# 4x7-segments_Arduino_shield.net
KiCad netlist of a schematic drawn in EAGLE
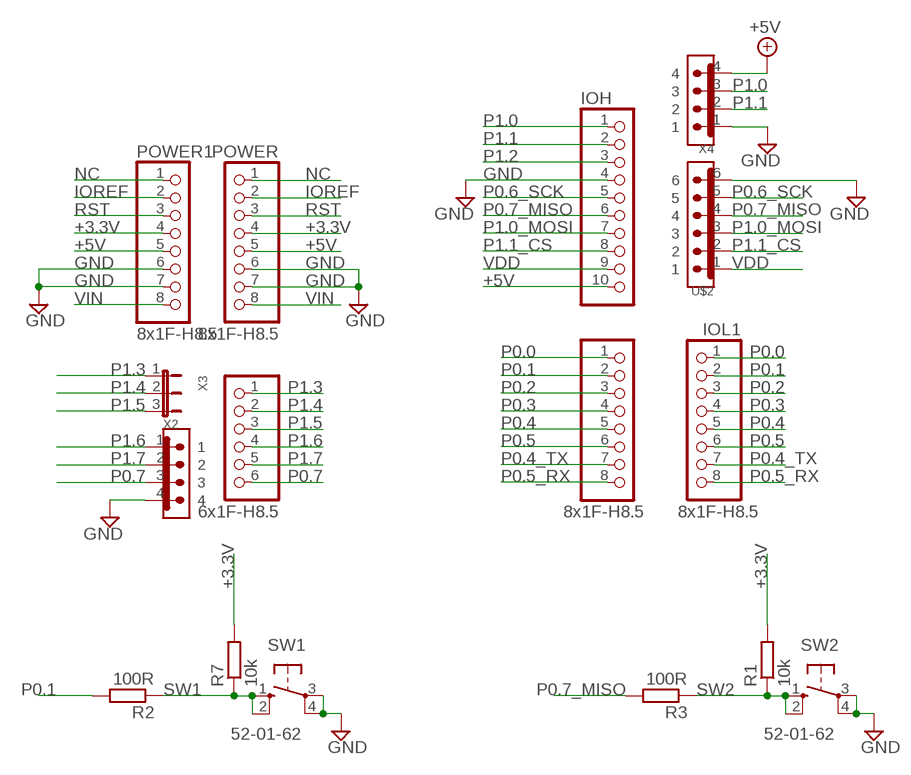
[diagram p0: schematic, sheet 1]
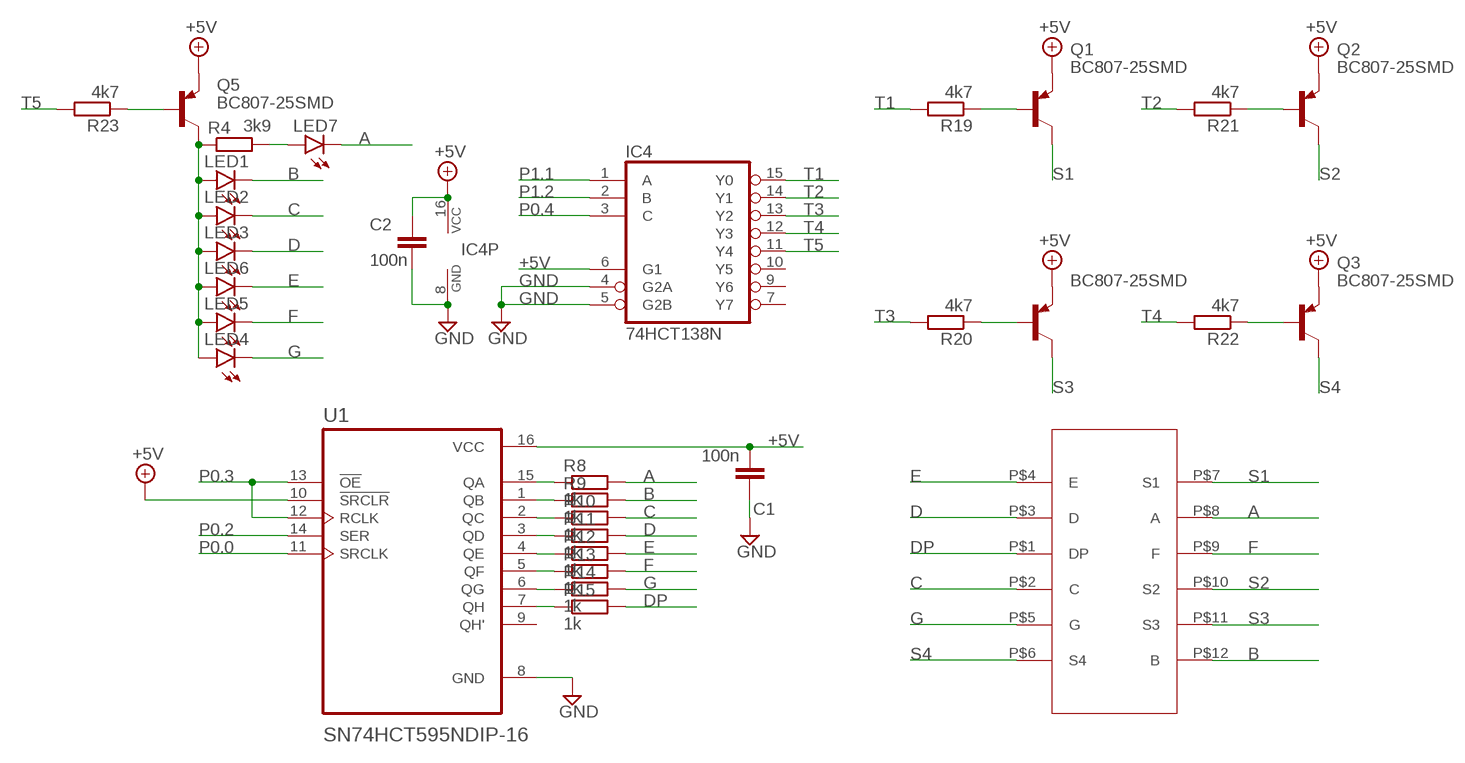
[diagram p1: schematic, sheet 2]
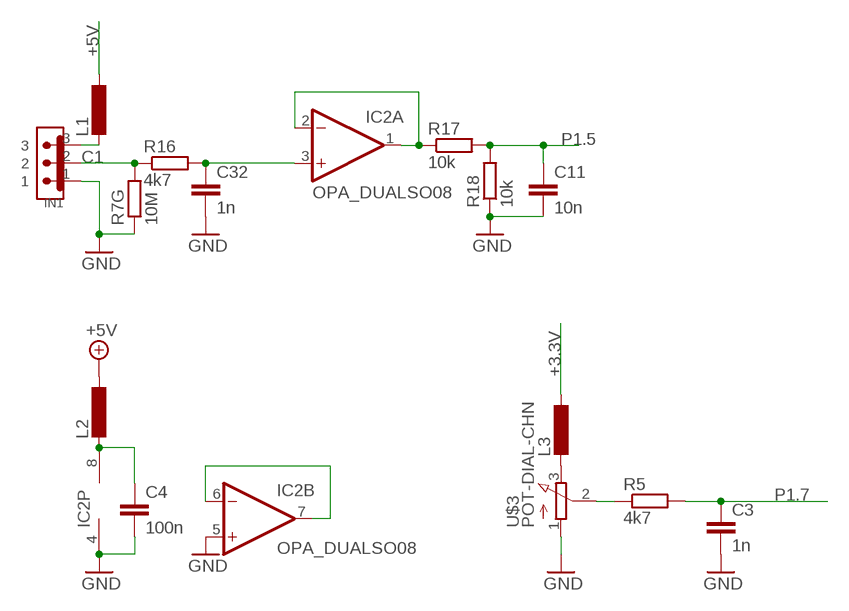
[diagram p2: schematic, sheet 3]

(export (version "E")
  (design (tool "Eeschema 10.0.6"))
  (components
    (comp (ref "AD")
      (value "6x1F-H8.5")
      (footprint "eagle-import:1X06")
      (libsource (lib "eagle-import") (part "PINHD-1X6"))
    )
    (comp (ref "IOH")
      (value "10x1F-H8.5")
      (footprint "eagle-import:1X10")
      (libsource (lib "eagle-import") (part "PINHD-1X10_ARD"))
    )
    (comp (ref "IOL")
      (value "8x1F-H8.5")
      (footprint "eagle-import:1X08")
      (libsource (lib "eagle-import") (part "PINHD-1X8"))
    )
    (comp (ref "IOL1")
      (value "8x1F-H8.5")
      (footprint "eagle-import:1X08")
      (libsource (lib "eagle-import") (part "PINHD-1X8"))
    )
    (comp (ref "POWER")
      (value "8x1F-H8.5")
      (footprint "eagle-import:1X08")
      (libsource (lib "eagle-import") (part "PINHD-1X8"))
    )
    (comp (ref "POWER1")
      (value "8x1F-H8.5")
      (footprint "eagle-import:1X08")
      (libsource (lib "eagle-import") (part "PINHD-1X8"))
    )
    (comp (ref "R1")
      (value "10k")
      (footprint "eagle-import:R0805")
      (libsource (lib "eagle-import") (part "Zoli2_R0805"))
    )
    (comp (ref "R2")
      (value "100R")
      (footprint "eagle-import:R0805")
      (libsource (lib "eagle-import") (part "R0805"))
    )
    (comp (ref "R3")
      (value "100R")
      (footprint "eagle-import:R0805")
      (libsource (lib "eagle-import") (part "R0805"))
    )
    (comp (ref "R7")
      (value "10k")
      (footprint "eagle-import:R0805")
      (libsource (lib "eagle-import") (part "Zoli2_R0805"))
    )
    (comp (ref "SW1")
      (value "52-01-62")
      (footprint "eagle-import:B3F-10XX")
      (fields (field (name "MPN") "B3F-1000"))
      (libsource (lib "eagle-import") (part "10-XX"))
    )
    (comp (ref "SW2")
      (value "52-01-62")
      (footprint "eagle-import:B3F-10XX")
      (fields (field (name "MPN") "B3F-1000"))
      (libsource (lib "eagle-import") (part "10-XX"))
    )
    (comp (ref "U$2")
      (value "MOLEX6")
      (footprint "eagle-import:MOLEXV6")
      (libsource (lib "eagle-import") (part "MOLEX6"))
    )
    (comp (ref "X2")
      (value "MOLEX4V")
      (footprint "eagle-import:MOLEXV4")
      (libsource (lib "eagle-import") (part "MOLEX4V"))
    )
    (comp (ref "X3")
      (value "JP2E")
      (footprint "eagle-import:JP2")
      (libsource (lib "eagle-import") (part "JP2E"))
    )
    (comp (ref "X4")
      (value "MOLEX4V")
      (footprint "eagle-import:MOLEXV4")
      (libsource (lib "eagle-import") (part "MOLEX4V"))
    )
    (comp (ref "C3")
      (value "1n")
      (footprint "eagle-import:C0805")
      (libsource (lib "eagle-import") (part "Zoli_C0805"))
    )
    (comp (ref "C4")
      (value "100n")
      (footprint "eagle-import:C0805")
      (libsource (lib "eagle-import") (part "Zoli2_C0805"))
    )
    (comp (ref "C11")
      (value "10n")
      (footprint "eagle-import:C0805")
      (libsource (lib "eagle-import") (part "C0805"))
    )
    (comp (ref "C32")
      (value "1n")
      (footprint "eagle-import:C0805")
      (libsource (lib "eagle-import") (part "Zoli_C0805"))
    )
    (comp (ref "IC2")
      (value "OPA_DUALSO08")
      (footprint "eagle-import:SO08")
      (libsource (lib "eagle-import") (part "OPA_DUALSO08"))
    )
    (comp (ref "IN1")
      (value "MOLEX3V")
      (footprint "eagle-import:MOLEXV3")
      (libsource (lib "eagle-import") (part "MOLEX3V"))
    )
    (comp (ref "L1")
      (value "L0805")
      (footprint "eagle-import:R0805")
      (libsource (lib "eagle-import") (part "L0805"))
    )
    (comp (ref "L2")
      (value "L0805")
      (footprint "eagle-import:R0805")
      (libsource (lib "eagle-import") (part "L0805"))
    )
    (comp (ref "L3")
      (value "L0805")
      (footprint "eagle-import:R0805")
      (libsource (lib "eagle-import") (part "L0805"))
    )
    (comp (ref "R5")
      (value "4k7")
      (footprint "eagle-import:R0805")
      (libsource (lib "eagle-import") (part "R0805"))
    )
    (comp (ref "R7G")
      (value "10M")
      (footprint "eagle-import:R0805")
      (libsource (lib "eagle-import") (part "R0805"))
    )
    (comp (ref "R16")
      (value "4k7")
      (footprint "eagle-import:R0805")
      (libsource (lib "eagle-import") (part "R0805"))
    )
    (comp (ref "R17")
      (value "10k")
      (footprint "eagle-import:R1206")
      (libsource (lib "eagle-import") (part "Zoli2_R1206"))
    )
    (comp (ref "R18")
      (value "10k")
      (footprint "eagle-import:R1206")
      (libsource (lib "eagle-import") (part "Zoli2_R1206"))
    )
    (comp (ref "U$3")
      (value "POT-DIAL-CHN")
      (footprint "eagle-import:POT5")
      (libsource (lib "eagle-import") (part "POT-DIAL-CHN"))
    )
    (comp (ref "C1")
      (value "100n")
      (footprint "eagle-import:C0805")
      (libsource (lib "eagle-import") (part "Zoli_C0805"))
    )
    (comp (ref "C2")
      (value "100n")
      (footprint "eagle-import:C0805")
      (libsource (lib "eagle-import") (part "Zoli_C0805"))
    )
    (comp (ref "IC4")
      (value "74HCT138N")
      (footprint "eagle-import:DIL16")
      (libsource (lib "eagle-import") (part "74138NHC"))
    )
    (comp (ref "LED1")
      (value "LEDCHIPLED_1206")
      (footprint "eagle-import:CHIPLED_1206")
      (libsource (lib "eagle-import") (part "LEDCHIPLED_1206"))
    )
    (comp (ref "LED2")
      (value "LEDCHIPLED_1206")
      (footprint "eagle-import:CHIPLED_1206")
      (libsource (lib "eagle-import") (part "LEDCHIPLED_1206"))
    )
    (comp (ref "LED3")
      (value "LEDCHIPLED_1206")
      (footprint "eagle-import:CHIPLED_1206")
      (libsource (lib "eagle-import") (part "LEDCHIPLED_1206"))
    )
    (comp (ref "LED4")
      (value "LEDCHIPLED_1206")
      (footprint "eagle-import:CHIPLED_1206")
      (libsource (lib "eagle-import") (part "LEDCHIPLED_1206"))
    )
    (comp (ref "LED5")
      (value "LEDCHIPLED_1206")
      (footprint "eagle-import:CHIPLED_1206")
      (libsource (lib "eagle-import") (part "LEDCHIPLED_1206"))
    )
    (comp (ref "LED6")
      (value "LEDCHIPLED_1206")
      (footprint "eagle-import:CHIPLED_1206")
      (libsource (lib "eagle-import") (part "LEDCHIPLED_1206"))
    )
    (comp (ref "LED7")
      (value "LEDCHIPLED_1206")
      (footprint "eagle-import:CHIPLED_1206")
      (libsource (lib "eagle-import") (part "LEDCHIPLED_1206"))
    )
    (comp (ref "Q1")
      (value "BC807-25SMD")
      (footprint "eagle-import:SOT23-BEC")
      (libsource (lib "eagle-import") (part "BC807SMD-25"))
    )
    (comp (ref "Q2")
      (value "BC807-25SMD")
      (footprint "eagle-import:SOT23-BEC")
      (libsource (lib "eagle-import") (part "BC807SMD-25"))
    )
    (comp (ref "Q3")
      (value "BC807-25SMD")
      (footprint "eagle-import:SOT23-BEC")
      (libsource (lib "eagle-import") (part "BC807SMD-25"))
    )
    (comp (ref "Q4")
      (value "BC807-25SMD")
      (footprint "eagle-import:SOT23-BEC")
      (libsource (lib "eagle-import") (part "BC807SMD-25"))
    )
    (comp (ref "Q5")
      (value "BC807-25SMD")
      (footprint "eagle-import:SOT23-BEC")
      (libsource (lib "eagle-import") (part "BC807SMD-25"))
    )
    (comp (ref "R4")
      (value "3k9")
      (footprint "eagle-import:R1206")
      (libsource (lib "eagle-import") (part "R1206"))
    )
    (comp (ref "R8")
      (value "1k")
      (footprint "eagle-import:R1206")
      (libsource (lib "eagle-import") (part "R1206"))
    )
    (comp (ref "R9")
      (value "1k")
      (footprint "eagle-import:R1206")
      (libsource (lib "eagle-import") (part "R1206"))
    )
    (comp (ref "R10")
      (value "1k")
      (footprint "eagle-import:R1206")
      (libsource (lib "eagle-import") (part "R1206"))
    )
    (comp (ref "R11")
      (value "1k")
      (footprint "eagle-import:R1206")
      (libsource (lib "eagle-import") (part "R1206"))
    )
    (comp (ref "R12")
      (value "1k")
      (footprint "eagle-import:R1206")
      (libsource (lib "eagle-import") (part "R1206"))
    )
    (comp (ref "R13")
      (value "1k")
      (footprint "eagle-import:R1206")
      (libsource (lib "eagle-import") (part "R1206"))
    )
    (comp (ref "R14")
      (value "1k")
      (footprint "eagle-import:R1206")
      (libsource (lib "eagle-import") (part "R1206"))
    )
    (comp (ref "R15")
      (value "1k")
      (footprint "eagle-import:R1206")
      (libsource (lib "eagle-import") (part "R1206"))
    )
    (comp (ref "R19")
      (value "4k7")
      (footprint "eagle-import:R0805")
      (libsource (lib "eagle-import") (part "R0805"))
    )
    (comp (ref "R20")
      (value "4k7")
      (footprint "eagle-import:R0805")
      (libsource (lib "eagle-import") (part "R0805"))
    )
    (comp (ref "R21")
      (value "4k7")
      (footprint "eagle-import:R0805")
      (libsource (lib "eagle-import") (part "R0805"))
    )
    (comp (ref "R22")
      (value "4k7")
      (footprint "eagle-import:R0805")
      (libsource (lib "eagle-import") (part "R0805"))
    )
    (comp (ref "R23")
      (value "4k7")
      (footprint "eagle-import:R0805")
      (libsource (lib "eagle-import") (part "R0805"))
    )
    (comp (ref "U$1")
      (value "SH5461AS")
      (footprint "eagle-import:SH5461AS")
      (libsource (lib "eagle-import") (part "SH5461AS"))
    )
    (comp (ref "U1")
      (value "SN74HCT595NDIP-16")
      (footprint "eagle-import:DIP794W45P254L1969H508Q16")
      (fields (field (name "MF") "Texas Instruments") (field (name "MP") "SN74HC595N"))
      (libsource (lib "eagle-import") (part "SN74HC595NDIP-16"))
    )
  )
  (nets
    (net (code "1") (name "+3.3V") (class "Default")
      (node (ref "L3") (pin "2") (pinfunction "2_2") (pintype "passive"))
      (node (ref "POWER") (pin "4") (pinfunction "4_4") (pintype "passive"))
      (node (ref "POWER1") (pin "4") (pinfunction "4_4") (pintype "passive"))
      (node (ref "R1") (pin "2") (pinfunction "2_2") (pintype "passive"))
      (node (ref "R7") (pin "2") (pinfunction "2_2") (pintype "passive"))
    )
    (net (code "2") (name "+5V") (class "Default")
      (node (ref "C1") (pin "1") (pinfunction "1_1") (pintype "passive"))
      (node (ref "C2") (pin "2") (pinfunction "2_2") (pintype "passive"))
      (node (ref "IC4") (pin "16") (pinfunction "VCC_16") (pintype "power_in"))
      (node (ref "IC4") (pin "6") (pinfunction "G1_6") (pintype "input"))
      (node (ref "IOH") (pin "10") (pinfunction "10_10") (pintype "passive"))
      (node (ref "L1") (pin "2") (pinfunction "2_2") (pintype "passive"))
      (node (ref "L2") (pin "2") (pinfunction "2_2") (pintype "passive"))
      (node (ref "POWER") (pin "5") (pinfunction "5_5") (pintype "passive"))
      (node (ref "POWER1") (pin "5") (pinfunction "5_5") (pintype "passive"))
      (node (ref "Q1") (pin "E") (pinfunction "E_E") (pintype "passive"))
      (node (ref "Q2") (pin "E") (pinfunction "E_E") (pintype "passive"))
      (node (ref "Q3") (pin "E") (pinfunction "E_E") (pintype "passive"))
      (node (ref "Q4") (pin "E") (pinfunction "E_E") (pintype "passive"))
      (node (ref "Q5") (pin "E") (pinfunction "E_E") (pintype "passive"))
      (node (ref "U1") (pin "10") (pinfunction "~{SRCLR}_10") (pintype "input"))
      (node (ref "U1") (pin "16") (pinfunction "VCC_16") (pintype "power_in"))
      (node (ref "X4") (pin "4") (pinfunction "4_4") (pintype "bidirectional"))
    )
    (net (code "3") (name "A") (class "Default")
      (node (ref "LED7") (pin "C") (pinfunction "C_C") (pintype "passive"))
      (node (ref "R8") (pin "2") (pinfunction "2_2") (pintype "passive"))
      (node (ref "U$1") (pin "P$8") (pinfunction "A_P$8") (pintype "input"))
    )
    (net (code "4") (name "B") (class "Default")
      (node (ref "LED1") (pin "C") (pinfunction "C_C") (pintype "passive"))
      (node (ref "R9") (pin "2") (pinfunction "2_2") (pintype "passive"))
      (node (ref "U$1") (pin "P$12") (pinfunction "B_P$12") (pintype "input"))
    )
    (net (code "5") (name "C") (class "Default")
      (node (ref "LED2") (pin "C") (pinfunction "C_C") (pintype "passive"))
      (node (ref "R10") (pin "2") (pinfunction "2_2") (pintype "passive"))
      (node (ref "U$1") (pin "P$2") (pinfunction "C_P$2") (pintype "input"))
    )
    (net (code "6") (name "C1") (class "Default")
      (node (ref "IN1") (pin "2") (pinfunction "2_2") (pintype "bidirectional"))
      (node (ref "R16") (pin "1") (pinfunction "1_1") (pintype "passive"))
      (node (ref "R7G") (pin "2") (pinfunction "2_2") (pintype "passive"))
    )
    (net (code "7") (name "D") (class "Default")
      (node (ref "LED3") (pin "C") (pinfunction "C_C") (pintype "passive"))
      (node (ref "R11") (pin "2") (pinfunction "2_2") (pintype "passive"))
      (node (ref "U$1") (pin "P$3") (pinfunction "D_P$3") (pintype "input"))
    )
    (net (code "8") (name "DP") (class "Default")
      (node (ref "R15") (pin "2") (pinfunction "2_2") (pintype "passive"))
      (node (ref "U$1") (pin "P$1") (pinfunction "DP_P$1") (pintype "input"))
    )
    (net (code "9") (name "E") (class "Default")
      (node (ref "LED6") (pin "C") (pinfunction "C_C") (pintype "passive"))
      (node (ref "R12") (pin "2") (pinfunction "2_2") (pintype "passive"))
      (node (ref "U$1") (pin "P$4") (pinfunction "E_P$4") (pintype "input"))
    )
    (net (code "10") (name "F") (class "Default")
      (node (ref "LED5") (pin "C") (pinfunction "C_C") (pintype "passive"))
      (node (ref "R13") (pin "2") (pinfunction "2_2") (pintype "passive"))
      (node (ref "U$1") (pin "P$9") (pinfunction "F_P$9") (pintype "input"))
    )
    (net (code "11") (name "G") (class "Default")
      (node (ref "LED4") (pin "C") (pinfunction "C_C") (pintype "passive"))
      (node (ref "R14") (pin "2") (pinfunction "2_2") (pintype "passive"))
      (node (ref "U$1") (pin "P$5") (pinfunction "G_P$5") (pintype "input"))
    )
    (net (code "12") (name "GND") (class "Default")
      (node (ref "C1") (pin "2") (pinfunction "2_2") (pintype "passive"))
      (node (ref "C11") (pin "1") (pinfunction "1_1") (pintype "passive"))
      (node (ref "C2") (pin "1") (pinfunction "1_1") (pintype "passive"))
      (node (ref "C3") (pin "1") (pinfunction "1_1") (pintype "passive"))
      (node (ref "C32") (pin "1") (pinfunction "1_1") (pintype "passive"))
      (node (ref "C4") (pin "1") (pinfunction "1_1") (pintype "passive"))
      (node (ref "IC2") (pin "4") (pinfunction "V-_4") (pintype "power_in"))
      (node (ref "IC2") (pin "5") (pinfunction "+IN_5") (pintype "input"))
      (node (ref "IC4") (pin "4") (pinfunction "G2A_4") (pintype "input"))
      (node (ref "IC4") (pin "5") (pinfunction "G2B_5") (pintype "input"))
      (node (ref "IC4") (pin "8") (pinfunction "GND_8") (pintype "power_in"))
      (node (ref "IN1") (pin "1") (pinfunction "1_1") (pintype "bidirectional"))
      (node (ref "IOH") (pin "4") (pinfunction "4_4") (pintype "passive"))
      (node (ref "POWER") (pin "6") (pinfunction "6_6") (pintype "passive"))
      (node (ref "POWER") (pin "7") (pinfunction "7_7") (pintype "passive"))
      (node (ref "POWER1") (pin "6") (pinfunction "6_6") (pintype "passive"))
      (node (ref "POWER1") (pin "7") (pinfunction "7_7") (pintype "passive"))
      (node (ref "R18") (pin "1") (pinfunction "1_1") (pintype "passive"))
      (node (ref "R7G") (pin "1") (pinfunction "1_1") (pintype "passive"))
      (node (ref "SW1") (pin "3") (pinfunction "P_3") (pintype "passive"))
      (node (ref "SW1") (pin "4") (pinfunction "P1_4") (pintype "passive"))
      (node (ref "SW2") (pin "3") (pinfunction "P_3") (pintype "passive"))
      (node (ref "SW2") (pin "4") (pinfunction "P1_4") (pintype "passive"))
      (node (ref "U$2") (pin "6") (pinfunction "6_6") (pintype "bidirectional"))
      (node (ref "U$3") (pin "1") (pinfunction "A_1") (pintype "passive"))
      (node (ref "U1") (pin "8") (pinfunction "GND_8") (pintype "power_in"))
      (node (ref "X2") (pin "4") (pinfunction "4_4") (pintype "bidirectional"))
      (node (ref "X4") (pin "1") (pinfunction "1_1") (pintype "bidirectional"))
    )
    (net (code "13") (name "IOREF") (class "Default")
      (node (ref "POWER") (pin "2") (pinfunction "2_2") (pintype "passive"))
      (node (ref "POWER1") (pin "2") (pinfunction "2_2") (pintype "passive"))
    )
    (net (code "14") (name "NC") (class "Default")
      (node (ref "POWER") (pin "1") (pinfunction "1_1") (pintype "passive"))
      (node (ref "POWER1") (pin "1") (pinfunction "1_1") (pintype "passive"))
    )
    (net (code "15") (name "Net-(IC2A-+IN)") (class "Default")
      (node (ref "C32") (pin "2") (pinfunction "2_2") (pintype "passive"))
      (node (ref "IC2") (pin "3") (pinfunction "+IN_3") (pintype "input"))
      (node (ref "R16") (pin "2") (pinfunction "2_2") (pintype "passive"))
    )
    (net (code "16") (name "Net-(IC2A--IN)") (class "Default")
      (node (ref "IC2") (pin "1") (pinfunction "OUT_1") (pintype "output"))
      (node (ref "IC2") (pin "2") (pinfunction "-IN_2") (pintype "input"))
      (node (ref "R17") (pin "1") (pinfunction "1_1") (pintype "passive"))
    )
    (net (code "17") (name "Net-(IC2B--IN)") (class "Default")
      (node (ref "IC2") (pin "6") (pinfunction "-IN_6") (pintype "input"))
      (node (ref "IC2") (pin "7") (pinfunction "OUT_7") (pintype "output"))
    )
    (net (code "18") (name "Net-(IC2C-V+)") (class "Default")
      (node (ref "C4") (pin "2") (pinfunction "2_2") (pintype "passive"))
      (node (ref "IC2") (pin "8") (pinfunction "V+_8") (pintype "power_in"))
      (node (ref "L2") (pin "1") (pinfunction "1_1") (pintype "passive"))
    )
    (net (code "19") (name "Net-(IN1-Pad3)") (class "Default")
      (node (ref "IN1") (pin "3") (pinfunction "3_3") (pintype "bidirectional"))
      (node (ref "L1") (pin "1") (pinfunction "1_1") (pintype "passive"))
    )
    (net (code "20") (name "Net-(LED1-PadA)") (class "Default")
      (node (ref "LED1") (pin "A") (pinfunction "A_A") (pintype "passive"))
      (node (ref "LED2") (pin "A") (pinfunction "A_A") (pintype "passive"))
      (node (ref "LED3") (pin "A") (pinfunction "A_A") (pintype "passive"))
      (node (ref "LED4") (pin "A") (pinfunction "A_A") (pintype "passive"))
      (node (ref "LED5") (pin "A") (pinfunction "A_A") (pintype "passive"))
      (node (ref "LED6") (pin "A") (pinfunction "A_A") (pintype "passive"))
      (node (ref "Q5") (pin "C") (pinfunction "C_C") (pintype "passive"))
      (node (ref "R4") (pin "1") (pinfunction "1_1") (pintype "passive"))
    )
    (net (code "21") (name "Net-(LED7-PadA)") (class "Default")
      (node (ref "LED7") (pin "A") (pinfunction "A_A") (pintype "passive"))
      (node (ref "R4") (pin "2") (pinfunction "2_2") (pintype "passive"))
    )
    (net (code "22") (name "Net-(Q1-PadB)") (class "Default")
      (node (ref "Q1") (pin "B") (pinfunction "B_B") (pintype "passive"))
      (node (ref "R19") (pin "1") (pinfunction "1_1") (pintype "passive"))
    )
    (net (code "23") (name "Net-(Q2-PadB)") (class "Default")
      (node (ref "Q2") (pin "B") (pinfunction "B_B") (pintype "passive"))
      (node (ref "R21") (pin "1") (pinfunction "1_1") (pintype "passive"))
    )
    (net (code "24") (name "Net-(Q3-PadB)") (class "Default")
      (node (ref "Q3") (pin "B") (pinfunction "B_B") (pintype "passive"))
      (node (ref "R22") (pin "1") (pinfunction "1_1") (pintype "passive"))
    )
    (net (code "25") (name "Net-(Q4-PadB)") (class "Default")
      (node (ref "Q4") (pin "B") (pinfunction "B_B") (pintype "passive"))
      (node (ref "R20") (pin "1") (pinfunction "1_1") (pintype "passive"))
    )
    (net (code "26") (name "Net-(Q5-PadB)") (class "Default")
      (node (ref "Q5") (pin "B") (pinfunction "B_B") (pintype "passive"))
      (node (ref "R23") (pin "1") (pinfunction "1_1") (pintype "passive"))
    )
    (net (code "27") (name "Net-(U$3-E)") (class "Default")
      (node (ref "L3") (pin "1") (pinfunction "1_1") (pintype "passive"))
      (node (ref "U$3") (pin "3") (pinfunction "E_3") (pintype "passive"))
    )
    (net (code "28") (name "Net-(U$3-S)") (class "Default")
      (node (ref "R5") (pin "1") (pinfunction "1_1") (pintype "passive"))
      (node (ref "U$3") (pin "2") (pinfunction "S_2") (pintype "passive"))
    )
    (net (code "29") (name "Net-(U1-QA)") (class "Default")
      (node (ref "R8") (pin "1") (pinfunction "1_1") (pintype "passive"))
      (node (ref "U1") (pin "15") (pinfunction "QA_15") (pintype "output"))
    )
    (net (code "30") (name "Net-(U1-QB)") (class "Default")
      (node (ref "R9") (pin "1") (pinfunction "1_1") (pintype "passive"))
      (node (ref "U1") (pin "1") (pinfunction "QB_1") (pintype "output"))
    )
    (net (code "31") (name "Net-(U1-QC)") (class "Default")
      (node (ref "R10") (pin "1") (pinfunction "1_1") (pintype "passive"))
      (node (ref "U1") (pin "2") (pinfunction "QC_2") (pintype "output"))
    )
    (net (code "32") (name "Net-(U1-QD)") (class "Default")
      (node (ref "R11") (pin "1") (pinfunction "1_1") (pintype "passive"))
      (node (ref "U1") (pin "3") (pinfunction "QD_3") (pintype "output"))
    )
    (net (code "33") (name "Net-(U1-QE)") (class "Default")
      (node (ref "R12") (pin "1") (pinfunction "1_1") (pintype "passive"))
      (node (ref "U1") (pin "4") (pinfunction "QE_4") (pintype "output"))
    )
    (net (code "34") (name "Net-(U1-QF)") (class "Default")
      (node (ref "R13") (pin "1") (pinfunction "1_1") (pintype "passive"))
      (node (ref "U1") (pin "5") (pinfunction "QF_5") (pintype "output"))
    )
    (net (code "35") (name "Net-(U1-QG)") (class "Default")
      (node (ref "R14") (pin "1") (pinfunction "1_1") (pintype "passive"))
      (node (ref "U1") (pin "6") (pinfunction "QG_6") (pintype "output"))
    )
    (net (code "36") (name "Net-(U1-QH)") (class "Default")
      (node (ref "R15") (pin "1") (pinfunction "1_1") (pintype "passive"))
      (node (ref "U1") (pin "7") (pinfunction "QH_7") (pintype "output"))
    )
    (net (code "37") (name "P0.0") (class "Default")
      (node (ref "IOL") (pin "1") (pinfunction "1_1") (pintype "passive"))
      (node (ref "IOL1") (pin "1") (pinfunction "1_1") (pintype "passive"))
      (node (ref "U1") (pin "11") (pinfunction "SRCLK_11") (pintype "input"))
    )
    (net (code "38") (name "P0.1") (class "Default")
      (node (ref "IOL") (pin "2") (pinfunction "2_2") (pintype "passive"))
      (node (ref "IOL1") (pin "2") (pinfunction "2_2") (pintype "passive"))
      (node (ref "R2") (pin "2") (pinfunction "2_2") (pintype "passive"))
    )
    (net (code "39") (name "P0.2") (class "Default")
      (node (ref "IOL") (pin "3") (pinfunction "3_3") (pintype "passive"))
      (node (ref "IOL1") (pin "3") (pinfunction "3_3") (pintype "passive"))
      (node (ref "U1") (pin "14") (pinfunction "SER_14") (pintype "input"))
    )
    (net (code "40") (name "P0.3") (class "Default")
      (node (ref "IOL") (pin "4") (pinfunction "4_4") (pintype "passive"))
      (node (ref "IOL1") (pin "4") (pinfunction "4_4") (pintype "passive"))
      (node (ref "U1") (pin "12") (pinfunction "RCLK_12") (pintype "input"))
      (node (ref "U1") (pin "13") (pinfunction "~{OE}_13") (pintype "input"))
    )
    (net (code "41") (name "P0.4") (class "Default")
      (node (ref "IC4") (pin "3") (pinfunction "C_3") (pintype "input"))
      (node (ref "IOL") (pin "5") (pinfunction "5_5") (pintype "passive"))
      (node (ref "IOL1") (pin "5") (pinfunction "5_5") (pintype "passive"))
    )
    (net (code "42") (name "P0.4_TX") (class "Default")
      (node (ref "IOL") (pin "7") (pinfunction "7_7") (pintype "passive"))
      (node (ref "IOL1") (pin "7") (pinfunction "7_7") (pintype "passive"))
    )
    (net (code "43") (name "P0.5") (class "Default")
      (node (ref "IOL") (pin "6") (pinfunction "6_6") (pintype "passive"))
      (node (ref "IOL1") (pin "6") (pinfunction "6_6") (pintype "passive"))
    )
    (net (code "44") (name "P0.5_RX") (class "Default")
      (node (ref "IOL") (pin "8") (pinfunction "8_8") (pintype "passive"))
      (node (ref "IOL1") (pin "8") (pinfunction "8_8") (pintype "passive"))
    )
    (net (code "45") (name "P0.6_SCK") (class "Default")
      (node (ref "IOH") (pin "5") (pinfunction "5_5") (pintype "passive"))
      (node (ref "U$2") (pin "5") (pinfunction "5_5") (pintype "bidirectional"))
    )
    (net (code "46") (name "P0.7") (class "Default")
      (node (ref "AD") (pin "6") (pinfunction "6_6") (pintype "passive"))
      (node (ref "X2") (pin "3") (pinfunction "3_3") (pintype "bidirectional"))
    )
    (net (code "47") (name "P0.7_MISO") (class "Default")
      (node (ref "IOH") (pin "6") (pinfunction "6_6") (pintype "passive"))
      (node (ref "R3") (pin "2") (pinfunction "2_2") (pintype "passive"))
      (node (ref "U$2") (pin "4") (pinfunction "4_4") (pintype "bidirectional"))
    )
    (net (code "48") (name "P1.0") (class "Default")
      (node (ref "IOH") (pin "1") (pinfunction "1_1") (pintype "passive"))
      (node (ref "X4") (pin "3") (pinfunction "3_3") (pintype "bidirectional"))
    )
    (net (code "49") (name "P1.0_MOSI") (class "Default")
      (node (ref "IOH") (pin "7") (pinfunction "7_7") (pintype "passive"))
      (node (ref "U$2") (pin "3") (pinfunction "3_3") (pintype "bidirectional"))
    )
    (net (code "50") (name "P1.1") (class "Default")
      (node (ref "IC4") (pin "1") (pinfunction "A_1") (pintype "input"))
      (node (ref "IOH") (pin "2") (pinfunction "2_2") (pintype "passive"))
      (node (ref "X4") (pin "2") (pinfunction "2_2") (pintype "bidirectional"))
    )
    (net (code "51") (name "P1.1_CS") (class "Default")
      (node (ref "IOH") (pin "8") (pinfunction "8_8") (pintype "passive"))
      (node (ref "U$2") (pin "2") (pinfunction "2_2") (pintype "bidirectional"))
    )
    (net (code "52") (name "P1.2") (class "Default")
      (node (ref "IC4") (pin "2") (pinfunction "B_2") (pintype "input"))
      (node (ref "IOH") (pin "3") (pinfunction "3_3") (pintype "passive"))
    )
    (net (code "53") (name "P1.3") (class "Default")
      (node (ref "AD") (pin "1") (pinfunction "1_1") (pintype "passive"))
      (node (ref "X3") (pin "1") (pinfunction "1_1") (pintype "passive"))
    )
    (net (code "54") (name "P1.4") (class "Default")
      (node (ref "AD") (pin "2") (pinfunction "2_2") (pintype "passive"))
      (node (ref "X3") (pin "2") (pinfunction "2_2") (pintype "passive"))
    )
    (net (code "55") (name "P1.5") (class "Default")
      (node (ref "AD") (pin "3") (pinfunction "3_3") (pintype "passive"))
      (node (ref "C11") (pin "2") (pinfunction "2_2") (pintype "passive"))
      (node (ref "R17") (pin "2") (pinfunction "2_2") (pintype "passive"))
      (node (ref "R18") (pin "2") (pinfunction "2_2") (pintype "passive"))
      (node (ref "X3") (pin "3") (pinfunction "3_3") (pintype "passive"))
    )
    (net (code "56") (name "P1.6") (class "Default")
      (node (ref "AD") (pin "4") (pinfunction "4_4") (pintype "passive"))
      (node (ref "X2") (pin "1") (pinfunction "1_1") (pintype "bidirectional"))
    )
    (net (code "57") (name "P1.7") (class "Default")
      (node (ref "AD") (pin "5") (pinfunction "5_5") (pintype "passive"))
      (node (ref "C3") (pin "2") (pinfunction "2_2") (pintype "passive"))
      (node (ref "R5") (pin "2") (pinfunction "2_2") (pintype "passive"))
      (node (ref "X2") (pin "2") (pinfunction "2_2") (pintype "bidirectional"))
    )
    (net (code "58") (name "RST") (class "Default")
      (node (ref "POWER") (pin "3") (pinfunction "3_3") (pintype "passive"))
      (node (ref "POWER1") (pin "3") (pinfunction "3_3") (pintype "passive"))
    )
    (net (code "59") (name "S1") (class "Default")
      (node (ref "Q1") (pin "C") (pinfunction "C_C") (pintype "passive"))
      (node (ref "U$1") (pin "P$7") (pinfunction "S1_P$7") (pintype "output"))
    )
    (net (code "60") (name "S2") (class "Default")
      (node (ref "Q2") (pin "C") (pinfunction "C_C") (pintype "passive"))
      (node (ref "U$1") (pin "P$10") (pinfunction "S2_P$10") (pintype "output"))
    )
    (net (code "61") (name "S3") (class "Default")
      (node (ref "Q4") (pin "C") (pinfunction "C_C") (pintype "passive"))
      (node (ref "U$1") (pin "P$11") (pinfunction "S3_P$11") (pintype "output"))
    )
    (net (code "62") (name "S4") (class "Default")
      (node (ref "Q3") (pin "C") (pinfunction "C_C") (pintype "passive"))
      (node (ref "U$1") (pin "P$6") (pinfunction "S4_P$6") (pintype "output"))
    )
    (net (code "63") (name "SW1") (class "Default")
      (node (ref "R2") (pin "1") (pinfunction "1_1") (pintype "passive"))
      (node (ref "R7") (pin "1") (pinfunction "1_1") (pintype "passive"))
      (node (ref "SW1") (pin "1") (pinfunction "S_1") (pintype "passive"))
      (node (ref "SW1") (pin "2") (pinfunction "S1_2") (pintype "passive"))
    )
    (net (code "64") (name "SW2") (class "Default")
      (node (ref "R1") (pin "1") (pinfunction "1_1") (pintype "passive"))
      (node (ref "R3") (pin "1") (pinfunction "1_1") (pintype "passive"))
      (node (ref "SW2") (pin "1") (pinfunction "S_1") (pintype "passive"))
      (node (ref "SW2") (pin "2") (pinfunction "S1_2") (pintype "passive"))
    )
    (net (code "65") (name "T1") (class "Default")
      (node (ref "IC4") (pin "15") (pinfunction "Y0_15") (pintype "output"))
      (node (ref "R19") (pin "2") (pinfunction "2_2") (pintype "passive"))
    )
    (net (code "66") (name "T2") (class "Default")
      (node (ref "IC4") (pin "14") (pinfunction "Y1_14") (pintype "output"))
      (node (ref "R21") (pin "2") (pinfunction "2_2") (pintype "passive"))
    )
    (net (code "67") (name "T3") (class "Default")
      (node (ref "IC4") (pin "13") (pinfunction "Y2_13") (pintype "output"))
      (node (ref "R20") (pin "2") (pinfunction "2_2") (pintype "passive"))
    )
    (net (code "68") (name "T4") (class "Default")
      (node (ref "IC4") (pin "12") (pinfunction "Y3_12") (pintype "output"))
      (node (ref "R22") (pin "2") (pinfunction "2_2") (pintype "passive"))
    )
    (net (code "69") (name "T5") (class "Default")
      (node (ref "IC4") (pin "11") (pinfunction "Y4_11") (pintype "output"))
      (node (ref "R23") (pin "2") (pinfunction "2_2") (pintype "passive"))
    )
    (net (code "70") (name "VDD") (class "Default")
      (node (ref "IOH") (pin "9") (pinfunction "9_9") (pintype "passive"))
      (node (ref "U$2") (pin "1") (pinfunction "1_1") (pintype "bidirectional"))
    )
    (net (code "71") (name "VIN") (class "Default")
      (node (ref "POWER") (pin "8") (pinfunction "8_8") (pintype "passive"))
      (node (ref "POWER1") (pin "8") (pinfunction "8_8") (pintype "passive"))
    )
    (net (code "72") (name "unconnected-(IC4A-Y5-Pad10)") (class "Default")
      (node (ref "IC4") (pin "10") (pinfunction "Y5_10") (pintype "output"))
    )
    (net (code "73") (name "unconnected-(IC4A-Y6-Pad9)") (class "Default")
      (node (ref "IC4") (pin "9") (pinfunction "Y6_9") (pintype "output"))
    )
    (net (code "74") (name "unconnected-(IC4A-Y7-Pad7)") (class "Default")
      (node (ref "IC4") (pin "7") (pinfunction "Y7_7") (pintype "output"))
    )
    (net (code "75") (name "unconnected-(U1-QH'-Pad9)") (class "Default")
      (node (ref "U1") (pin "9") (pinfunction "QH'_9") (pintype "output"))
    )
  )
)
